# 3DR-Radio-915-v13_site.net
KiCad netlist of a schematic drawn in EAGLE
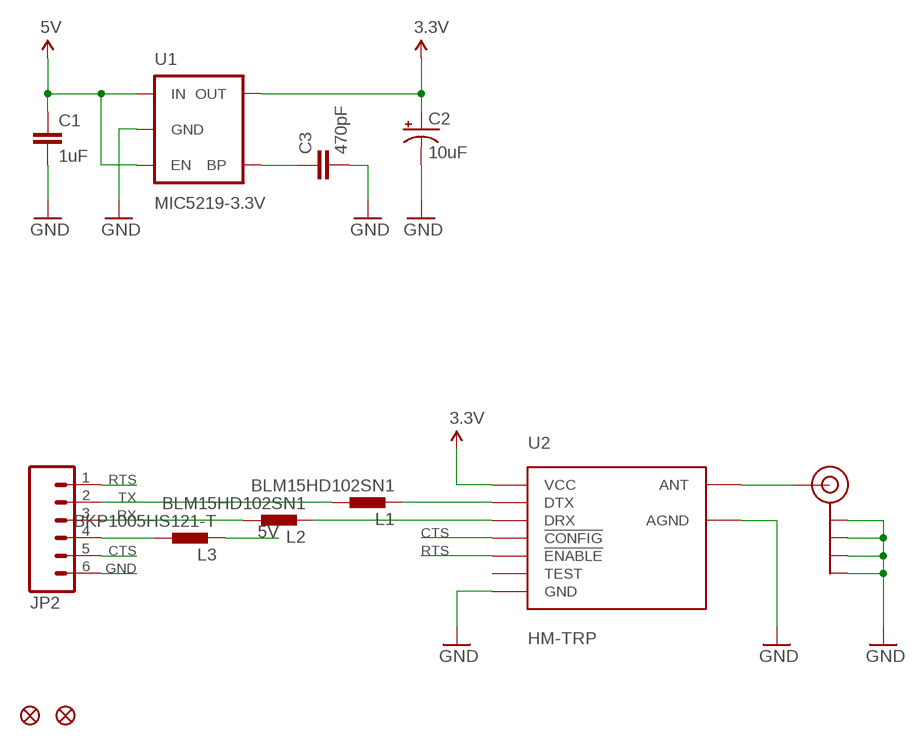
[diagram p0: schematic, sheet 1]

(export (version "E")
  (design (tool "Eeschema 10.0.6"))
  (components
    (comp (ref "C1")
      (value "1uF")
      (footprint "eagle-import:0402-CAP")
      (libsource (lib "eagle-import") (part "CAP0402-CAP"))
    )
    (comp (ref "C2")
      (value "10uF")
      (footprint "eagle-import:EIA3216")
      (libsource (lib "eagle-import") (part "CAP_POL1206"))
    )
    (comp (ref "C3")
      (value "470pF")
      (footprint "eagle-import:0402-CAP")
      (libsource (lib "eagle-import") (part "CAP0402-CAP"))
    )
    (comp (ref "J$2")
      (value "SMA_EDGE")
      (footprint "eagle-import:SMA-EDGE")
      (libsource (lib "eagle-import") (part "SMA_EDGE"))
    )
    (comp (ref "JP1")
      (value "FIDUCIAL1X2")
      (footprint "eagle-import:FIDUCIAL-1X2")
      (libsource (lib "eagle-import") (part "FIDUCIAL1X2"))
    )
    (comp (ref "JP2")
      (value "M06SIP")
      (footprint "eagle-import:1X06")
      (libsource (lib "eagle-import") (part "M06SIP"))
    )
    (comp (ref "JP3")
      (value "FIDUCIAL1X2")
      (footprint "eagle-import:FIDUCIAL-1X2")
      (libsource (lib "eagle-import") (part "FIDUCIAL1X2"))
    )
    (comp (ref "L1")
      (value "BLM15HD102SN1")
      (footprint "eagle-import:0402-IND")
      (libsource (lib "eagle-import") (part "INDUCTOR-0402"))
    )
    (comp (ref "L2")
      (value "BLM15HD102SN1")
      (footprint "eagle-import:0402-IND")
      (libsource (lib "eagle-import") (part "INDUCTOR-0402"))
    )
    (comp (ref "L3")
      (value "BKP1005HS121-T")
      (footprint "eagle-import:0402-IND")
      (libsource (lib "eagle-import") (part "INDUCTOR-0402"))
    )
    (comp (ref "U1")
      (value "MIC5219-3.3V")
      (footprint "eagle-import:SOT23-5")
      (libsource (lib "eagle-import") (part "V_REG_LDOSMD"))
    )
    (comp (ref "U2")
      (value "HM-TRP")
      (footprint "eagle-import:HM-TRP-SMD")
      (libsource (lib "eagle-import") (part "HM-TRPSMD"))
    )
  )
  (nets
    (net (code "1") (name "/CTS") (class "Default")
      (node (ref "JP2") (pin "5") (pinfunction "5_5") (pintype "passive"))
      (node (ref "U2") (pin "!CONFIG") (pinfunction "~{CONFIG}_!CONFIG") (pintype "input"))
    )
    (net (code "2") (name "/RTS") (class "Default")
      (node (ref "JP2") (pin "1") (pinfunction "1_1") (pintype "passive"))
      (node (ref "U2") (pin "!ENABLE") (pinfunction "~{ENABLE}_!ENABLE") (pintype "input"))
    )
    (net (code "3") (name "/RX") (class "Default")
      (node (ref "JP2") (pin "3") (pinfunction "3_3") (pintype "passive"))
      (node (ref "L2") (pin "P$1") (pinfunction "1_P$1") (pintype "passive"))
    )
    (net (code "4") (name "/TX") (class "Default")
      (node (ref "JP2") (pin "2") (pinfunction "2_2") (pintype "passive"))
      (node (ref "L1") (pin "P$1") (pinfunction "1_P$1") (pintype "passive"))
    )
    (net (code "5") (name "3.3V") (class "Default")
      (node (ref "C2") (pin "A") (pinfunction "+_A") (pintype "passive"))
      (node (ref "U1") (pin "5") (pinfunction "OUT_5") (pintype "passive"))
      (node (ref "U2") (pin "VCC") (pinfunction "VCC_VCC") (pintype "power_in"))
    )
    (net (code "6") (name "5V") (class "Default")
      (node (ref "C1") (pin "1") (pinfunction "1_1") (pintype "passive"))
      (node (ref "L3") (pin "P$2") (pinfunction "2_P$2") (pintype "passive"))
      (node (ref "U1") (pin "1") (pinfunction "IN_1") (pintype "input"))
      (node (ref "U1") (pin "3") (pinfunction "EN_3") (pintype "input"))
    )
    (net (code "7") (name "GND") (class "Default")
      (node (ref "C1") (pin "2") (pinfunction "2_2") (pintype "passive"))
      (node (ref "C2") (pin "C") (pinfunction "-_C") (pintype "passive"))
      (node (ref "C3") (pin "2") (pinfunction "2_2") (pintype "passive"))
      (node (ref "J$2") (pin "GND@0") (pinfunction "GND_GND@0") (pintype "bidirectional"))
      (node (ref "J$2") (pin "GND@1") (pinfunction "GND_GND@1") (pintype "bidirectional"))
      (node (ref "J$2") (pin "GND@2") (pinfunction "GND_GND@2") (pintype "bidirectional"))
      (node (ref "J$2") (pin "GND@3") (pinfunction "GND_GND@3") (pintype "bidirectional"))
      (node (ref "JP2") (pin "6") (pinfunction "6_6") (pintype "passive"))
      (node (ref "U1") (pin "2") (pinfunction "GND_2") (pintype "input"))
      (node (ref "U2") (pin "AGND") (pinfunction "AGND_AGND") (pintype "power_in"))
      (node (ref "U2") (pin "GND") (pinfunction "GND_GND") (pintype "power_in"))
    )
    (net (code "8") (name "Net-(J$2-SIGNAL)") (class "Default")
      (node (ref "J$2") (pin "SIG") (pinfunction "SIGNAL_SIG") (pintype "bidirectional"))
      (node (ref "U2") (pin "ANT") (pinfunction "ANT_ANT") (pintype "bidirectional"))
    )
    (net (code "9") (name "Net-(L1-2)") (class "Default")
      (node (ref "L1") (pin "P$2") (pinfunction "2_P$2") (pintype "passive"))
      (node (ref "U2") (pin "DTX") (pinfunction "DTX_DTX") (pintype "output"))
    )
    (net (code "10") (name "Net-(L2-2)") (class "Default")
      (node (ref "L2") (pin "P$2") (pinfunction "2_P$2") (pintype "passive"))
      (node (ref "U2") (pin "DRX") (pinfunction "DRX_DRX") (pintype "input"))
    )
    (net (code "11") (name "Net-(L3-1)") (class "Default")
      (node (ref "JP2") (pin "4") (pinfunction "4_4") (pintype "passive"))
      (node (ref "L3") (pin "P$1") (pinfunction "1_P$1") (pintype "passive"))
    )
    (net (code "12") (name "Net-(U1-BP)") (class "Default")
      (node (ref "C3") (pin "1") (pinfunction "1_1") (pintype "passive"))
      (node (ref "U1") (pin "4") (pinfunction "BP_4") (pintype "input"))
    )
    (net (code "13") (name "unconnected-(U2-PadTEST)") (class "Default")
      (node (ref "U2") (pin "TEST") (pinfunction "TEST_TEST") (pintype "no_connect"))
    )
  )
)
